# main.net
KiCad netlist of a schematic drawn in EAGLE
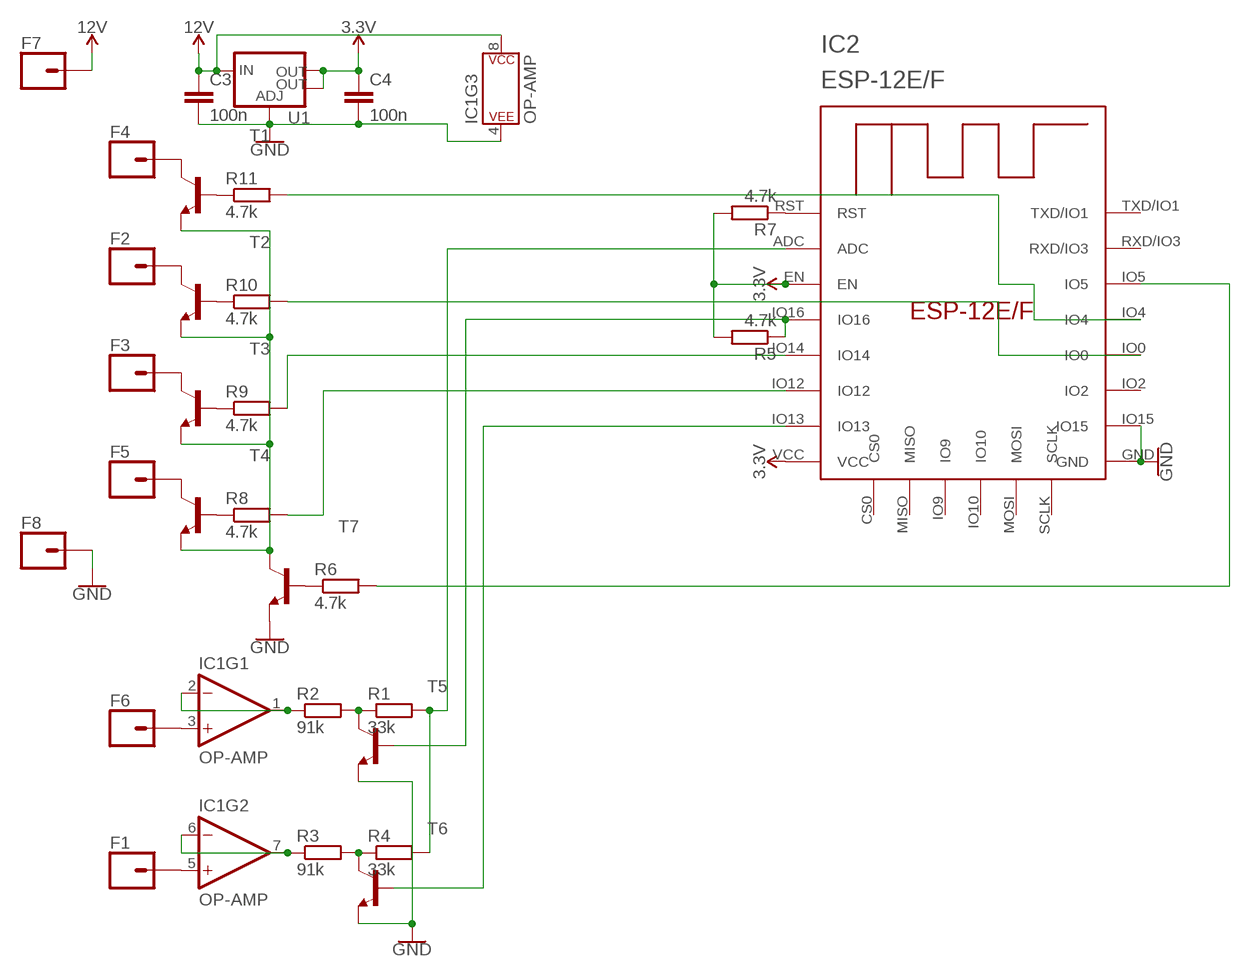
[diagram p0: schematic, sheet 1]

(export (version "E")
  (design (tool "Eeschema 10.0.6"))
  (components
    (comp (ref "C3")
      (value "100n")
      (footprint "eagle-import:C0805K")
      (libsource (lib "eagle-import") (part "C-EUC0805K"))
    )
    (comp (ref "C4")
      (value "100n")
      (footprint "eagle-import:C0805K")
      (libsource (lib "eagle-import") (part "C-EUC0805K"))
    )
    (comp (ref "F1")
      (value "CONN_01OFFSET")
      (footprint "eagle-import:1X01_OFFSET")
      (libsource (lib "eagle-import") (part "CONN_01OFFSET"))
    )
    (comp (ref "F2")
      (value "CONN_01OFFSET")
      (footprint "eagle-import:1X01_OFFSET")
      (libsource (lib "eagle-import") (part "CONN_01OFFSET"))
    )
    (comp (ref "F3")
      (value "CONN_01OFFSET")
      (footprint "eagle-import:1X01_OFFSET")
      (libsource (lib "eagle-import") (part "CONN_01OFFSET"))
    )
    (comp (ref "F4")
      (value "CONN_01OFFSET")
      (footprint "eagle-import:1X01_OFFSET")
      (libsource (lib "eagle-import") (part "CONN_01OFFSET"))
    )
    (comp (ref "F5")
      (value "CONN_01OFFSET")
      (footprint "eagle-import:1X01_OFFSET")
      (libsource (lib "eagle-import") (part "CONN_01OFFSET"))
    )
    (comp (ref "F6")
      (value "CONN_01OFFSET")
      (footprint "eagle-import:1X01_OFFSET")
      (libsource (lib "eagle-import") (part "CONN_01OFFSET"))
    )
    (comp (ref "F7")
      (value "CONN_01OFFSET")
      (footprint "eagle-import:1X01_OFFSET")
      (libsource (lib "eagle-import") (part "CONN_01OFFSET"))
    )
    (comp (ref "F8")
      (value "CONN_01OFFSET")
      (footprint "eagle-import:1X01_OFFSET")
      (libsource (lib "eagle-import") (part "CONN_01OFFSET"))
    )
    (comp (ref "IC1")
      (value "OP-AMP")
      (footprint "eagle-import:SO08")
      (libsource (lib "eagle-import") (part "OPAMP-DUALU"))
    )
    (comp (ref "IC2")
      (value "ESP-12E/F")
      (footprint "eagle-import:ESP-12E")
      (libsource (lib "eagle-import") (part "ESP-12E/F"))
    )
    (comp (ref "R1")
      (value "33k")
      (footprint "eagle-import:R0805")
      (libsource (lib "eagle-import") (part "R-EU_R0805"))
    )
    (comp (ref "R2")
      (value "91k")
      (footprint "eagle-import:R0805")
      (libsource (lib "eagle-import") (part "R-EU_R0805"))
    )
    (comp (ref "R3")
      (value "91k")
      (footprint "eagle-import:R0805")
      (libsource (lib "eagle-import") (part "R-EU_R0805"))
    )
    (comp (ref "R4")
      (value "33k")
      (footprint "eagle-import:R0805")
      (libsource (lib "eagle-import") (part "R-EU_R0805"))
    )
    (comp (ref "R5")
      (value "4.7k")
      (footprint "eagle-import:R0805")
      (libsource (lib "eagle-import") (part "R-EU_R0805"))
    )
    (comp (ref "R6")
      (value "4.7k")
      (footprint "eagle-import:R0805")
      (libsource (lib "eagle-import") (part "R-EU_R0805"))
    )
    (comp (ref "R7")
      (value "4.7k")
      (footprint "eagle-import:R0805")
      (libsource (lib "eagle-import") (part "R-EU_R0805"))
    )
    (comp (ref "R8")
      (value "4.7k")
      (footprint "eagle-import:R0805")
      (libsource (lib "eagle-import") (part "R-EU_R0805"))
    )
    (comp (ref "R9")
      (value "4.7k")
      (footprint "eagle-import:R0805")
      (libsource (lib "eagle-import") (part "R-EU_R0805"))
    )
    (comp (ref "R10")
      (value "4.7k")
      (footprint "eagle-import:R0805")
      (libsource (lib "eagle-import") (part "R-EU_R0805"))
    )
    (comp (ref "R11")
      (value "4.7k")
      (footprint "eagle-import:R0805")
      (libsource (lib "eagle-import") (part "R-EU_R0805"))
    )
    (comp (ref "T1")
      (value "MMBT5551LT1-NPN-SOT23-BEC")
      (footprint "eagle-import:SOT23-BEC")
      (libsource (lib "eagle-import") (part "-NPN-SOT23-BECMMBT5551LT1"))
    )
    (comp (ref "T2")
      (value "MMBT5551LT1-NPN-SOT23-BEC")
      (footprint "eagle-import:SOT23-BEC")
      (libsource (lib "eagle-import") (part "-NPN-SOT23-BECMMBT5551LT1"))
    )
    (comp (ref "T3")
      (value "MMBT5551LT1-NPN-SOT23-BEC")
      (footprint "eagle-import:SOT23-BEC")
      (libsource (lib "eagle-import") (part "-NPN-SOT23-BECMMBT5551LT1"))
    )
    (comp (ref "T4")
      (value "MMBT5551LT1-NPN-SOT23-BEC")
      (footprint "eagle-import:SOT23-BEC")
      (libsource (lib "eagle-import") (part "-NPN-SOT23-BECMMBT5551LT1"))
    )
    (comp (ref "T5")
      (value "MMBT5551LT1-NPN-SOT23-BEC")
      (footprint "eagle-import:SOT23-BEC")
      (libsource (lib "eagle-import") (part "-NPN-SOT23-BECMMBT5551LT1"))
    )
    (comp (ref "T6")
      (value "MMBT5551LT1-NPN-SOT23-BEC")
      (footprint "eagle-import:SOT23-BEC")
      (libsource (lib "eagle-import") (part "-NPN-SOT23-BECMMBT5551LT1"))
    )
    (comp (ref "T7")
      (value "MMBT5551LT1-NPN-SOT23-BEC")
      (footprint "eagle-import:SOT23-BEC")
      (libsource (lib "eagle-import") (part "-NPN-SOT23-BECMMBT5551LT1"))
    )
    (comp (ref "U1")
      (value "V_REG_LM1117SOT223")
      (footprint "eagle-import:SOT223")
      (libsource (lib "eagle-import") (part "V_REG_LM1117SOT223"))
    )
  )
  (nets
    (net (code "1") (name "3.3V") (class "Default")
      (node (ref "C4") (pin "1") (pinfunction "1_1") (pintype "passive"))
      (node (ref "IC2") (pin "EN") (pinfunction "EN_EN") (pintype "bidirectional"))
      (node (ref "IC2") (pin "VCC") (pinfunction "VCC_VCC") (pintype "power_in"))
      (node (ref "R5") (pin "2") (pinfunction "2_2") (pintype "passive"))
      (node (ref "R7") (pin "2") (pinfunction "2_2") (pintype "passive"))
      (node (ref "U1") (pin "2") (pinfunction "OUT_2") (pintype "output"))
      (node (ref "U1") (pin "4") (pinfunction "OUT_4") (pintype "output"))
    )
    (net (code "2") (name "12V") (class "Default")
      (node (ref "C3") (pin "1") (pinfunction "1_1") (pintype "passive"))
      (node (ref "F7") (pin "1") (pinfunction "1_1") (pintype "passive"))
      (node (ref "IC1") (pin "8") (pinfunction "P$V+_8") (pintype "bidirectional"))
      (node (ref "U1") (pin "3") (pinfunction "IN_3") (pintype "input"))
    )
    (net (code "3") (name "GND") (class "Default")
      (node (ref "C3") (pin "2") (pinfunction "2_2") (pintype "passive"))
      (node (ref "C4") (pin "2") (pinfunction "2_2") (pintype "passive"))
      (node (ref "F8") (pin "1") (pinfunction "1_1") (pintype "passive"))
      (node (ref "IC1") (pin "4") (pinfunction "P$V-_4") (pintype "bidirectional"))
      (node (ref "IC2") (pin "GND") (pinfunction "GND_GND") (pintype "power_in"))
      (node (ref "IC2") (pin "IO15") (pinfunction "IO15_IO15") (pintype "bidirectional"))
      (node (ref "T5") (pin "E") (pinfunction "E_E") (pintype "passive"))
      (node (ref "T6") (pin "E") (pinfunction "E_E") (pintype "passive"))
      (node (ref "T7") (pin "E") (pinfunction "E_E") (pintype "passive"))
      (node (ref "U1") (pin "1") (pinfunction "ADJ_1") (pintype "input"))
    )
    (net (code "4") (name "Net-(F2-Pad1)") (class "Default")
      (node (ref "F2") (pin "1") (pinfunction "1_1") (pintype "passive"))
      (node (ref "T2") (pin "C") (pinfunction "C_C") (pintype "passive"))
    )
    (net (code "5") (name "Net-(F3-Pad1)") (class "Default")
      (node (ref "F3") (pin "1") (pinfunction "1_1") (pintype "passive"))
      (node (ref "T3") (pin "C") (pinfunction "C_C") (pintype "passive"))
    )
    (net (code "6") (name "Net-(F4-Pad1)") (class "Default")
      (node (ref "F4") (pin "1") (pinfunction "1_1") (pintype "passive"))
      (node (ref "T1") (pin "C") (pinfunction "C_C") (pintype "passive"))
    )
    (net (code "7") (name "Net-(F5-Pad1)") (class "Default")
      (node (ref "F5") (pin "1") (pinfunction "1_1") (pintype "passive"))
      (node (ref "T4") (pin "C") (pinfunction "C_C") (pintype "passive"))
    )
    (net (code "8") (name "Net-(IC1A-+IN)") (class "Default")
      (node (ref "F6") (pin "1") (pinfunction "1_1") (pintype "passive"))
      (node (ref "IC1") (pin "3") (pinfunction "+IN_3") (pintype "input"))
    )
    (net (code "9") (name "Net-(IC1A--IN)") (class "Default")
      (node (ref "IC1") (pin "1") (pinfunction "OUT_1") (pintype "output"))
      (node (ref "IC1") (pin "2") (pinfunction "-IN_2") (pintype "input"))
      (node (ref "R2") (pin "1") (pinfunction "1_1") (pintype "passive"))
    )
    (net (code "10") (name "Net-(IC1B-+IN)") (class "Default")
      (node (ref "F1") (pin "1") (pinfunction "1_1") (pintype "passive"))
      (node (ref "IC1") (pin "5") (pinfunction "+IN_5") (pintype "input"))
    )
    (net (code "11") (name "Net-(IC1B--IN)") (class "Default")
      (node (ref "IC1") (pin "6") (pinfunction "-IN_6") (pintype "input"))
      (node (ref "IC1") (pin "7") (pinfunction "OUT_7") (pintype "output"))
      (node (ref "R3") (pin "1") (pinfunction "1_1") (pintype "passive"))
    )
    (net (code "12") (name "Net-(IC2-PadADC)") (class "Default")
      (node (ref "IC2") (pin "ADC") (pinfunction "ADC_ADC") (pintype "bidirectional"))
      (node (ref "R1") (pin "2") (pinfunction "2_2") (pintype "passive"))
      (node (ref "R4") (pin "2") (pinfunction "2_2") (pintype "passive"))
    )
    (net (code "13") (name "Net-(IC2-PadIO0)") (class "Default")
      (node (ref "IC2") (pin "IO0") (pinfunction "IO0_IO0") (pintype "bidirectional"))
      (node (ref "R10") (pin "2") (pinfunction "2_2") (pintype "passive"))
    )
    (net (code "14") (name "Net-(IC2-PadIO4)") (class "Default")
      (node (ref "IC2") (pin "IO4") (pinfunction "IO4_IO4") (pintype "bidirectional"))
      (node (ref "R11") (pin "2") (pinfunction "2_2") (pintype "passive"))
    )
    (net (code "15") (name "Net-(IC2-PadIO5)") (class "Default")
      (node (ref "IC2") (pin "IO5") (pinfunction "IO5_IO5") (pintype "bidirectional"))
      (node (ref "R6") (pin "2") (pinfunction "2_2") (pintype "passive"))
    )
    (net (code "16") (name "Net-(IC2-PadIO12)") (class "Default")
      (node (ref "IC2") (pin "IO12") (pinfunction "IO12_IO12") (pintype "bidirectional"))
      (node (ref "R8") (pin "2") (pinfunction "2_2") (pintype "passive"))
    )
    (net (code "17") (name "Net-(IC2-PadIO13)") (class "Default")
      (node (ref "IC2") (pin "IO13") (pinfunction "IO13_IO13") (pintype "bidirectional"))
      (node (ref "T6") (pin "B") (pinfunction "B_B") (pintype "passive"))
    )
    (net (code "18") (name "Net-(IC2-PadIO14)") (class "Default")
      (node (ref "IC2") (pin "IO14") (pinfunction "IO14_IO14") (pintype "bidirectional"))
      (node (ref "R9") (pin "2") (pinfunction "2_2") (pintype "passive"))
    )
    (net (code "19") (name "Net-(IC2-PadIO16)") (class "Default")
      (node (ref "IC2") (pin "IO16") (pinfunction "IO16_IO16") (pintype "bidirectional"))
      (node (ref "R5") (pin "1") (pinfunction "1_1") (pintype "passive"))
      (node (ref "T5") (pin "B") (pinfunction "B_B") (pintype "passive"))
    )
    (net (code "20") (name "Net-(IC2-PadRST)") (class "Default")
      (node (ref "IC2") (pin "RST") (pinfunction "RST_RST") (pintype "input"))
      (node (ref "R7") (pin "1") (pinfunction "1_1") (pintype "passive"))
    )
    (net (code "21") (name "Net-(R1-Pad1)") (class "Default")
      (node (ref "R1") (pin "1") (pinfunction "1_1") (pintype "passive"))
      (node (ref "R2") (pin "2") (pinfunction "2_2") (pintype "passive"))
      (node (ref "T5") (pin "C") (pinfunction "C_C") (pintype "passive"))
    )
    (net (code "22") (name "Net-(R3-Pad2)") (class "Default")
      (node (ref "R3") (pin "2") (pinfunction "2_2") (pintype "passive"))
      (node (ref "R4") (pin "1") (pinfunction "1_1") (pintype "passive"))
      (node (ref "T6") (pin "C") (pinfunction "C_C") (pintype "passive"))
    )
    (net (code "23") (name "Net-(R6-Pad1)") (class "Default")
      (node (ref "R6") (pin "1") (pinfunction "1_1") (pintype "passive"))
      (node (ref "T7") (pin "B") (pinfunction "B_B") (pintype "passive"))
    )
    (net (code "24") (name "Net-(R8-Pad1)") (class "Default")
      (node (ref "R8") (pin "1") (pinfunction "1_1") (pintype "passive"))
      (node (ref "T4") (pin "B") (pinfunction "B_B") (pintype "passive"))
    )
    (net (code "25") (name "Net-(R9-Pad1)") (class "Default")
      (node (ref "R9") (pin "1") (pinfunction "1_1") (pintype "passive"))
      (node (ref "T3") (pin "B") (pinfunction "B_B") (pintype "passive"))
    )
    (net (code "26") (name "Net-(R10-Pad1)") (class "Default")
      (node (ref "R10") (pin "1") (pinfunction "1_1") (pintype "passive"))
      (node (ref "T2") (pin "B") (pinfunction "B_B") (pintype "passive"))
    )
    (net (code "27") (name "Net-(R11-Pad1)") (class "Default")
      (node (ref "R11") (pin "1") (pinfunction "1_1") (pintype "passive"))
      (node (ref "T1") (pin "B") (pinfunction "B_B") (pintype "passive"))
    )
    (net (code "28") (name "Net-(T1-PadE)") (class "Default")
      (node (ref "T1") (pin "E") (pinfunction "E_E") (pintype "passive"))
      (node (ref "T2") (pin "E") (pinfunction "E_E") (pintype "passive"))
      (node (ref "T3") (pin "E") (pinfunction "E_E") (pintype "passive"))
      (node (ref "T4") (pin "E") (pinfunction "E_E") (pintype "passive"))
      (node (ref "T7") (pin "C") (pinfunction "C_C") (pintype "passive"))
    )
    (net (code "29") (name "unconnected-(IC2-PadCS0)") (class "Default")
      (node (ref "IC2") (pin "CS0") (pinfunction "CS0_CS0") (pintype "bidirectional"))
    )
    (net (code "30") (name "unconnected-(IC2-PadIO2)") (class "Default")
      (node (ref "IC2") (pin "IO2") (pinfunction "IO2_IO2") (pintype "bidirectional"))
    )
    (net (code "31") (name "unconnected-(IC2-PadIO9)") (class "Default")
      (node (ref "IC2") (pin "IO9") (pinfunction "IO9_IO9") (pintype "bidirectional"))
    )
    (net (code "32") (name "unconnected-(IC2-PadIO10)") (class "Default")
      (node (ref "IC2") (pin "IO10") (pinfunction "IO10_IO10") (pintype "bidirectional"))
    )
    (net (code "33") (name "unconnected-(IC2-PadMISO)") (class "Default")
      (node (ref "IC2") (pin "MISO") (pinfunction "MISO_MISO") (pintype "bidirectional"))
    )
    (net (code "34") (name "unconnected-(IC2-PadMOSI)") (class "Default")
      (node (ref "IC2") (pin "MOSI") (pinfunction "MOSI_MOSI") (pintype "bidirectional"))
    )
    (net (code "35") (name "unconnected-(IC2-PadRXD{slash}IO3)") (class "Default")
      (node (ref "IC2") (pin "RXD/IO3") (pinfunction "RXD/IO3_RXD/IO3") (pintype "bidirectional"))
    )
    (net (code "36") (name "unconnected-(IC2-PadSCLK)") (class "Default")
      (node (ref "IC2") (pin "SCLK") (pinfunction "SCLK_SCLK") (pintype "bidirectional"))
    )
    (net (code "37") (name "unconnected-(IC2-PadTXD{slash}IO1)") (class "Default")
      (node (ref "IC2") (pin "TXD/IO1") (pinfunction "TXD/IO1_TXD/IO1") (pintype "bidirectional"))
    )
  )
)
